# ETH_RJ45.net
KiCad netlist of a schematic drawn in Altium Designer
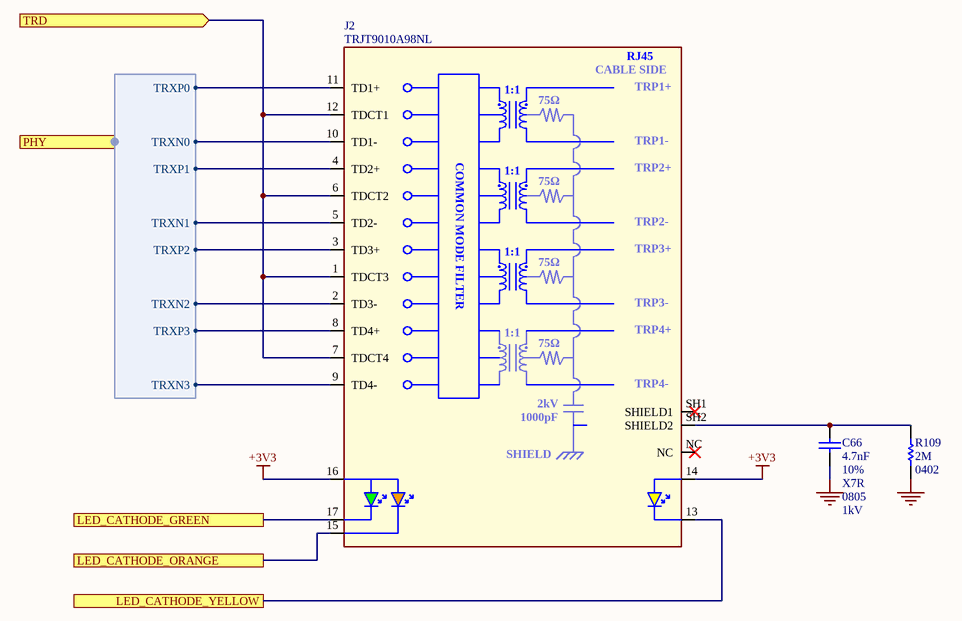
[diagram p0: ETH_RJ45.SchDoc]

(export (version "E")
  (design (tool "Eeschema 10.0.6"))
  (components
    (comp (ref "C66")
      (value "4.7nF")
      (footprint "CAP-0805")
      (description "CAP CHIP 0805 4.7nF 10% 1000V X7R")
      (fields
        (field (name "TOLERANCE") "10%")
        (field (name "DIELECTRIC") "X7R")
        (field (name "CASE CODE (IMPERIAL)") "0805")
        (field (name "MANUFACTURER") "PSA Shenzen")
        (field (name "VOLTAGE") "1kV")
        (field (name "PART NUMBER") "FV21X472K102ECG")
      )
      (libsource (lib "Clean") (part "CAP"))
    )
    (comp (ref "J2")
      (value "TRJT9010A98NL")
      (footprint "TRJT9010A98NL")
      (fields (field (name "MANUFACTURER") "TRXCOM"))
      (libsource (lib "Clean") (part "TRJT9010A98NL"))
    )
    (comp (ref "R109")
      (value "2M")
      (footprint "RES-0402")
      (description "RES CHIP 0402 2M 1% 1/16W")
      (fields
        (field (name "PART NUMBER") "RC0402FR-072ML")
        (field (name "CASE CODE (IMPERIAL)") "0402")
        (field (name "MANUFACTURER") "YAGEO")
      )
      (libsource (lib "Clean") (part "RES"))
    )
  )
  (nets
    (net (code "2") (name "+3V3") (class "Default")
      (node (ref "J2") (pin "14") (pinfunction "YELLOW_ANODE_14") (pintype "passive"))
      (node (ref "J2") (pin "16") (pinfunction "COMMON_ANODE_16") (pintype "passive"))
    )
    (net (code "3") (name "/LED_CATHODE_GREEN") (class "Default")
      (node (ref "J2") (pin "17") (pinfunction "GREEN_CATHODE_17") (pintype "passive"))
    )
    (net (code "4") (name "/LED_CATHODE_ORANGE") (class "Default")
      (node (ref "J2") (pin "15") (pinfunction "ORANGE_CATHODE_15") (pintype "passive"))
    )
    (net (code "5") (name "/LED_CATHODE_YELLOW") (class "Default")
      (node (ref "J2") (pin "13") (pinfunction "YELLOW_CATHODE_13") (pintype "passive"))
    )
    (net (code "6") (name "/TRD") (class "Default")
      (node (ref "J2") (pin "1") (pinfunction "TDCT3_1") (pintype "passive"))
      (node (ref "J2") (pin "12") (pinfunction "TDCT1_12") (pintype "passive"))
      (node (ref "J2") (pin "6") (pinfunction "TDCT2_6") (pintype "passive"))
      (node (ref "J2") (pin "7") (pinfunction "TDCT4_7") (pintype "passive"))
    )
    (net (code "7") (name "/TRXN0") (class "Default")
      (node (ref "J2") (pin "10") (pinfunction "TD1-_10") (pintype "passive"))
    )
    (net (code "8") (name "/TRXN1") (class "Default")
      (node (ref "J2") (pin "5") (pinfunction "TD2-_5") (pintype "passive"))
    )
    (net (code "9") (name "/TRXN2") (class "Default")
      (node (ref "J2") (pin "2") (pinfunction "TD3-_2") (pintype "passive"))
    )
    (net (code "10") (name "/TRXN3") (class "Default")
      (node (ref "J2") (pin "9") (pinfunction "TD4-_9") (pintype "passive"))
    )
    (net (code "11") (name "/TRXP0") (class "Default")
      (node (ref "J2") (pin "11") (pinfunction "TD1+_11") (pintype "passive"))
    )
    (net (code "12") (name "/TRXP1") (class "Default")
      (node (ref "J2") (pin "4") (pinfunction "TD2+_4") (pintype "passive"))
    )
    (net (code "13") (name "/TRXP2") (class "Default")
      (node (ref "J2") (pin "3") (pinfunction "TD3+_3") (pintype "passive"))
    )
    (net (code "14") (name "/TRXP3") (class "Default")
      (node (ref "J2") (pin "8") (pinfunction "TD4+_8") (pintype "passive"))
    )
    (net (code "16") (name "GND") (class "Default")
      (node (ref "C66") (pin "2") (pinfunction "2_2") (pintype "passive"))
      (node (ref "R109") (pin "1") (pinfunction "1_1") (pintype "passive"))
    )
    (net (code "17") (name "Net-(J2-SHIELD2)") (class "Default")
      (node (ref "C66") (pin "1") (pinfunction "1_1") (pintype "passive"))
      (node (ref "J2") (pin "SH2") (pinfunction "SHIELD2_SH2") (pintype "passive"))
      (node (ref "R109") (pin "2") (pinfunction "2_2") (pintype "passive"))
    )
    (net (code "18") (name "unconnected-(J2-PadNC)") (class "Default")
      (node (ref "J2") (pin "NC") (pinfunction "NC_NC") (pintype "passive+no_connect"))
    )
    (net (code "19") (name "unconnected-(J2-SHIELD1-PadSH1)") (class "Default")
      (node (ref "J2") (pin "SH1") (pinfunction "SHIELD1_SH1") (pintype "passive+no_connect"))
    )
  )
)
